# PowerSupply.net
KiCad netlist of a schematic drawn in Altium Designer
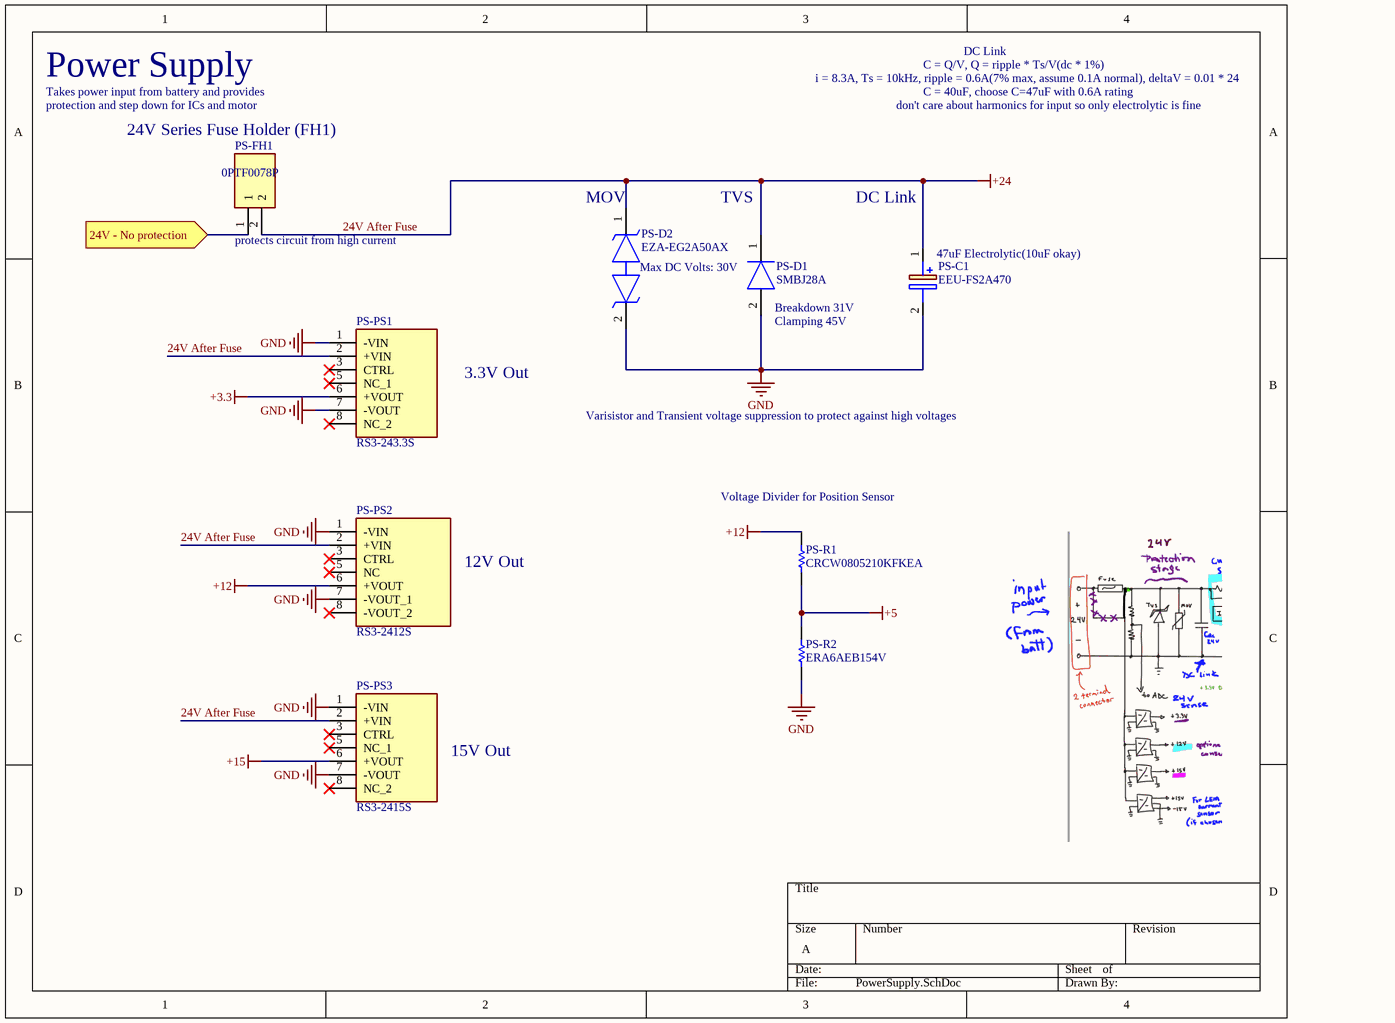
[diagram p0: PowerSupply.SchDoc]

(export (version "E")
  (design (tool "Eeschema 10.0.6"))
  (components
    (comp (ref "PS-C1")
      (value "EEU-FS2A470")
      (footprint "SamacSys:CAPPRD350W65D800H1650")
      (description "Capacitor Polarised 47uF")
      (fields (field (name "MOUSER PART NUMBER") "667-EEU-FS2A470"))
      (libsource (lib "*") (part "EEU-FS2A470"))
    )
    (comp (ref "PS-D1")
      (value "SMBJ28A")
      (footprint "SamacSys:DIOM5436X261N")
      (description "Diode")
      (fields (field (name "MOUSER PART NUMBER") "576-SMBJ28A"))
      (libsource (lib "*") (part "SMBJ28A"))
    )
    (comp (ref "PS-D2")
      (value "EZA-EG2A50AX")
      (footprint "SamacSys:DIONC1005X43N")
      (description "TVS Diode (Bi-directional)")
      (fields (field (name "MOUSER PART NUMBER") "667-EZA-EG2A50AX"))
      (libsource (lib "*") (part "EZA-EG2A50AX"))
    )
    (comp (ref "PS-FH1")
      (value "0PTF0078P")
      (footprint "SamacSys:0PTF0078P")
      (description "Undefined or Miscellaneous")
      (fields (field (name "MOUSER PART NUMBER") "576-0PTF0078P"))
      (libsource (lib "*") (part "0PTF0078P"))
    )
    (comp (ref "PS-PS1")
      (value "RS3-243.3S")
      (footprint "SamacSys:RS32433S")
      (description "Power Supply")
      (fields (field (name "MOUSER PART NUMBER") "919-RS3-243.3S"))
      (libsource (lib "*") (part "RS3-243.3S"))
    )
    (comp (ref "PS-PS2")
      (value "RS3-2412S")
      (footprint "RS32415S")
      (description "Power Supply 12V")
      (fields (field (name "MOUSER PART NUMBER") "919-RS3-2412S") (field (name "RS PART NUMBER") "1669097"))
      (libsource (lib "ee_453_yourname") (part "RS3-2412S"))
    )
    (comp (ref "PS-PS3")
      (value "RS3-2415S")
      (footprint "RS32415S")
      (description "Power Supply")
      (fields (field (name "MOUSER PART NUMBER") "919-RS3-2415S"))
      (libsource (lib "ee_453_yourname") (part "RS3-2415S"))
    )
    (comp (ref "PS-R1")
      (value "CRCW0805210KFKEA")
      (footprint "RESC2013X50X30LL20T20")
      (fields (field (name "MANUFACTURER") "Vishay Dale"))
      (libsource (lib "Altium Content Vault") (part "RES"))
    )
    (comp (ref "PS-R2")
      (value "ERA6AEB154V")
      (footprint "RESC2013X60X40LL20T25")
      (fields (field (name "MANUFACTURER") "Panasonic"))
      (libsource (lib "Altium Content Vault") (part "RES"))
    )
  )
  (nets
    (net (code "1") (name "+3.3") (class "Default")
      (node (ref "PS-PS1") (pin "6") (pinfunction "+VOUT_6") (pintype "passive"))
    )
    (net (code "2") (name "+5") (class "Default")
      (node (ref "PS-R1") (pin "1") (pinfunction "1_1") (pintype "passive"))
      (node (ref "PS-R2") (pin "2") (pinfunction "2_2") (pintype "passive"))
    )
    (net (code "3") (name "+12") (class "Default")
      (node (ref "PS-PS2") (pin "6") (pinfunction "+VOUT_6") (pintype "passive"))
      (node (ref "PS-R1") (pin "2") (pinfunction "2_2") (pintype "passive"))
    )
    (net (code "4") (name "+15") (class "Default")
      (node (ref "PS-PS3") (pin "6") (pinfunction "+VOUT_6") (pintype "passive"))
    )
    (net (code "5") (name "+24") (class "Default")
      (node (ref "PS-C1") (pin "1") (pinfunction "+_1") (pintype "passive"))
      (node (ref "PS-D1") (pin "1") (pinfunction "K_1") (pintype "passive"))
      (node (ref "PS-D2") (pin "1") (pinfunction "1_1") (pintype "passive"))
      (node (ref "PS-FH1") (pin "2") (pinfunction "2_2") (pintype "passive"))
      (node (ref "PS-PS1") (pin "2") (pinfunction "+VIN_2") (pintype "passive"))
      (node (ref "PS-PS2") (pin "2") (pinfunction "+VIN_2") (pintype "passive"))
      (node (ref "PS-PS3") (pin "2") (pinfunction "+VIN_2") (pintype "passive"))
    )
    (net (code "6") (name "/24V - No protection") (class "Default")
      (node (ref "PS-FH1") (pin "1") (pinfunction "1_1") (pintype "passive"))
    )
    (net (code "7") (name "GND") (class "Default")
      (node (ref "PS-C1") (pin "2") (pinfunction "-_2") (pintype "passive"))
      (node (ref "PS-D1") (pin "2") (pinfunction "A_2") (pintype "passive"))
      (node (ref "PS-D2") (pin "2") (pinfunction "2_2") (pintype "passive"))
      (node (ref "PS-PS1") (pin "1") (pinfunction "-VIN_1") (pintype "passive"))
      (node (ref "PS-PS1") (pin "7") (pinfunction "-VOUT_7") (pintype "passive"))
      (node (ref "PS-PS2") (pin "1") (pinfunction "-VIN_1") (pintype "passive"))
      (node (ref "PS-PS2") (pin "7") (pinfunction "-VOUT_1_7") (pintype "passive"))
      (node (ref "PS-PS3") (pin "1") (pinfunction "-VIN_1") (pintype "passive"))
      (node (ref "PS-PS3") (pin "7") (pinfunction "-VOUT_7") (pintype "passive"))
      (node (ref "PS-R2") (pin "1") (pinfunction "1_1") (pintype "passive"))
    )
    (net (code "8") (name "unconnected-(PS-PS1-CTRL-Pad3)") (class "Default")
      (node (ref "PS-PS1") (pin "3") (pinfunction "CTRL_3") (pintype "passive+no_connect"))
    )
    (net (code "9") (name "unconnected-(PS-PS1-NC_1-Pad5)") (class "Default")
      (node (ref "PS-PS1") (pin "5") (pinfunction "NC_1_5") (pintype "passive+no_connect"))
    )
    (net (code "10") (name "unconnected-(PS-PS1-NC_2-Pad8)") (class "Default")
      (node (ref "PS-PS1") (pin "8") (pinfunction "NC_2_8") (pintype "passive+no_connect"))
    )
    (net (code "11") (name "unconnected-(PS-PS2--VOUT_2-Pad8)") (class "Default")
      (node (ref "PS-PS2") (pin "8") (pinfunction "-VOUT_2_8") (pintype "passive+no_connect"))
    )
    (net (code "12") (name "unconnected-(PS-PS2-CTRL-Pad3)") (class "Default")
      (node (ref "PS-PS2") (pin "3") (pinfunction "CTRL_3") (pintype "passive+no_connect"))
    )
    (net (code "13") (name "unconnected-(PS-PS2-NC-Pad5)") (class "Default")
      (node (ref "PS-PS2") (pin "5") (pinfunction "NC_5") (pintype "passive+no_connect"))
    )
    (net (code "14") (name "unconnected-(PS-PS3-CTRL-Pad3)") (class "Default")
      (node (ref "PS-PS3") (pin "3") (pinfunction "CTRL_3") (pintype "passive+no_connect"))
    )
    (net (code "15") (name "unconnected-(PS-PS3-NC_1-Pad5)") (class "Default")
      (node (ref "PS-PS3") (pin "5") (pinfunction "NC_1_5") (pintype "passive+no_connect"))
    )
    (net (code "16") (name "unconnected-(PS-PS3-NC_2-Pad8)") (class "Default")
      (node (ref "PS-PS3") (pin "8") (pinfunction "NC_2_8") (pintype "passive+no_connect"))
    )
  )
)
